# CAN.net
KiCad netlist of a schematic drawn in Altium Designer
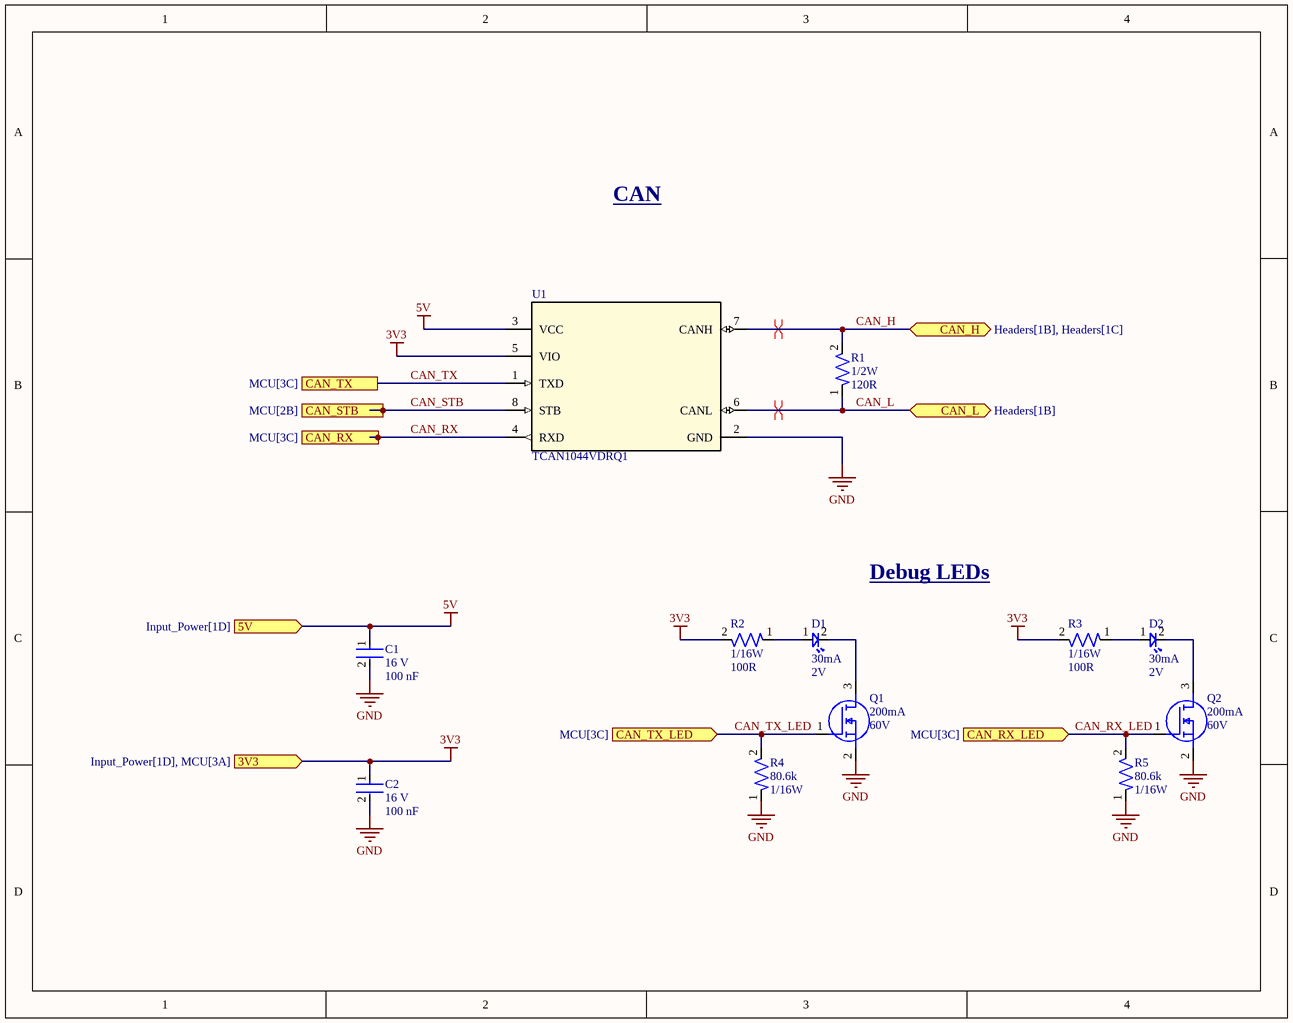
[diagram p0: CAN.SchDoc]

(export (version "E")
  (design (tool "Eeschema 10.0.6"))
  (components
    (comp (ref "C1")
      (value "CC0402KRX7R7BB104")
      (footprint "CAP-0402")
      (description "CAP CER 0.1UF 16V X7R 0402")
      (fields (field (name "VOLTAGE RATING") "16 V") (field (name "CAPACITANCE") "100 nF"))
      (libsource (lib "JLC_25") (part "CAP-0.1U-0001"))
    )
    (comp (ref "C2")
      (value "CC0402KRX7R7BB104")
      (footprint "CAP-0402")
      (description "CAP CER 0.1UF 16V X7R 0402")
      (fields (field (name "VOLTAGE RATING") "16 V") (field (name "CAPACITANCE") "100 nF"))
      (libsource (lib "JLC_25") (part "CAP-0.1U-0001"))
    )
    (comp (ref "D1")
      (value "BL-HKC36G-AV-TRB")
      (footprint "LED-0603")
      (description "LED YELLOW CLEAR 0603 SMD")
      (fields (field (name "FORWARD CURRENT") "30mA") (field (name "FORWARD VOLTAGE") "2V"))
      (libsource (lib "JLC_25") (part "LED-0001"))
    )
    (comp (ref "D2")
      (value "BL-HKC36G-AV-TRB")
      (footprint "LED-0603")
      (description "LED YELLOW CLEAR 0603 SMD")
      (fields (field (name "FORWARD CURRENT") "30mA") (field (name "FORWARD VOLTAGE") "2V"))
      (libsource (lib "JLC_25") (part "LED-0001"))
    )
    (comp (ref "Q1")
      (value "T2N7002AK,LM")
      (footprint "IC-SOT23-3")
      (description "MOSFET N-CH 60V 200MA SOT23")
      (fields (field (name "CONTINUOUS CURRENT") "200mA") (field (name "VOLTAGE") "60V"))
      (libsource (lib "JLC_25") (part "NMOS-200MA-0001"))
    )
    (comp (ref "Q2")
      (value "T2N7002AK,LM")
      (footprint "IC-SOT23-3")
      (description "MOSFET N-CH 60V 200MA SOT23")
      (fields (field (name "CONTINUOUS CURRENT") "200mA") (field (name "VOLTAGE") "60V"))
      (libsource (lib "JLC_25") (part "NMOS-200MA-0001"))
    )
    (comp (ref "R1")
      (value "RC1210FR-07120RL")
      (footprint "RES-1210")
      (description "RES 120 OHM 1% 1/2W 1210")
      (fields
        (field (name "TOLERANCE") "1%")
        (field (name "POWER") "1/2W")
        (field (name "RESISTANCE") "120R")
      )
      (libsource (lib "JLC_25") (part "RES-120-0001"))
    )
    (comp (ref "R2")
      (value "RC0402FR-07100RL")
      (footprint "RES-0402")
      (description "RES 100 OHM 1% 1/16W 0402")
      (fields
        (field (name "TOLERANCE") "1%")
        (field (name "POWER") "1/16W")
        (field (name "RESISTANCE") "100R")
      )
      (libsource (lib "JLC_25") (part "RES-100-0001"))
    )
    (comp (ref "R3")
      (value "RC0402FR-07100RL")
      (footprint "RES-0402")
      (description "RES 100 OHM 1% 1/16W 0402")
      (fields
        (field (name "TOLERANCE") "1%")
        (field (name "POWER") "1/16W")
        (field (name "RESISTANCE") "100R")
      )
      (libsource (lib "JLC_25") (part "RES-100-0001"))
    )
    (comp (ref "R4")
      (value "RC0402FR-0780K6L")
      (footprint "RES-0402")
      (description "80.6 kOhms ±1% 0.063W, 1/16W Chip Resistor 0402 (1005 Metric) Moisture Resistant Thick Film")
      (fields
        (field (name "TOLERANCE") "1%")
        (field (name "RESISTANCE") "80.6k")
        (field (name "POWER") "1/16W")
      )
      (libsource (lib "JLC_25") (part "RES-80.6k-0001"))
    )
    (comp (ref "R5")
      (value "RC0402FR-0780K6L")
      (footprint "RES-0402")
      (description "80.6 kOhms ±1% 0.063W, 1/16W Chip Resistor 0402 (1005 Metric) Moisture Resistant Thick Film")
      (fields
        (field (name "TOLERANCE") "1%")
        (field (name "RESISTANCE") "80.6k")
        (field (name "POWER") "1/16W")
      )
      (libsource (lib "JLC_25") (part "RES-80.6k-0001"))
    )
    (comp (ref "U1")
      (value "TCAN1044VDRQ1")
      (footprint "IC-8SOIC")
      (description "IC TRANSCEIVER 1/1 8SOIC")
      (libsource (lib "JLC_25") (part "IC-CAN-0001"))
    )
  )
  (nets
    (net (code "1") (name "/CAN_H") (class "Default")
      (node (ref "R1") (pin "2") (pinfunction "2_2") (pintype "passive"))
      (node (ref "U1") (pin "7") (pinfunction "CANH_7") (pintype "bidirectional"))
    )
    (net (code "2") (name "/CAN_L") (class "Default")
      (node (ref "R1") (pin "1") (pinfunction "1_1") (pintype "passive"))
      (node (ref "U1") (pin "6") (pinfunction "CANL_6") (pintype "bidirectional"))
    )
    (net (code "3") (name "/CAN_RX") (class "Default")
      (node (ref "U1") (pin "4") (pinfunction "RXD_4") (pintype "output"))
    )
    (net (code "4") (name "/CAN_RX_LED") (class "Default")
      (node (ref "Q2") (pin "1") (pinfunction "G_1") (pintype "passive"))
      (node (ref "R5") (pin "2") (pinfunction "2_2") (pintype "passive"))
    )
    (net (code "5") (name "/CAN_STB") (class "Default")
      (node (ref "U1") (pin "8") (pinfunction "STB_8") (pintype "input"))
    )
    (net (code "6") (name "/CAN_TX") (class "Default")
      (node (ref "U1") (pin "1") (pinfunction "TXD_1") (pintype "input"))
    )
    (net (code "7") (name "/CAN_TX_LED") (class "Default")
      (node (ref "Q1") (pin "1") (pinfunction "G_1") (pintype "passive"))
      (node (ref "R4") (pin "2") (pinfunction "2_2") (pintype "passive"))
    )
    (net (code "8") (name "3V3") (class "Default")
      (node (ref "C2") (pin "1") (pinfunction "1_1") (pintype "passive"))
      (node (ref "R2") (pin "2") (pinfunction "2_2") (pintype "passive"))
      (node (ref "R3") (pin "2") (pinfunction "2_2") (pintype "passive"))
      (node (ref "U1") (pin "5") (pinfunction "VIO_5") (pintype "power_in"))
    )
    (net (code "9") (name "5V") (class "Default")
      (node (ref "C1") (pin "1") (pinfunction "1_1") (pintype "passive"))
      (node (ref "U1") (pin "3") (pinfunction "VCC_3") (pintype "power_in"))
    )
    (net (code "10") (name "GND") (class "Default")
      (node (ref "C1") (pin "2") (pinfunction "2_2") (pintype "passive"))
      (node (ref "C2") (pin "2") (pinfunction "2_2") (pintype "passive"))
      (node (ref "Q1") (pin "2") (pinfunction "S_2") (pintype "passive"))
      (node (ref "Q2") (pin "2") (pinfunction "S_2") (pintype "passive"))
      (node (ref "R4") (pin "1") (pinfunction "1_1") (pintype "passive"))
      (node (ref "R5") (pin "1") (pinfunction "1_1") (pintype "passive"))
      (node (ref "U1") (pin "2") (pinfunction "GND_2") (pintype "power_in"))
    )
    (net (code "11") (name "Net-(D1-Pad1)") (class "Default")
      (node (ref "D1") (pin "1") (pinfunction "1_1") (pintype "passive"))
      (node (ref "R2") (pin "1") (pinfunction "1_1") (pintype "passive"))
    )
    (net (code "12") (name "Net-(D2-Pad1)") (class "Default")
      (node (ref "D2") (pin "1") (pinfunction "1_1") (pintype "passive"))
      (node (ref "R3") (pin "1") (pinfunction "1_1") (pintype "passive"))
    )
    (net (code "13") (name "Net-(Q1-D)") (class "Default")
      (node (ref "D1") (pin "2") (pinfunction "2_2") (pintype "passive"))
      (node (ref "Q1") (pin "3") (pinfunction "D_3") (pintype "passive"))
    )
    (net (code "14") (name "Net-(Q2-D)") (class "Default")
      (node (ref "D2") (pin "2") (pinfunction "2_2") (pintype "passive"))
      (node (ref "Q2") (pin "3") (pinfunction "D_3") (pintype "passive"))
    )
  )
)
